# DE-270124.net
KiCad netlist of a schematic drawn in Altium Designer
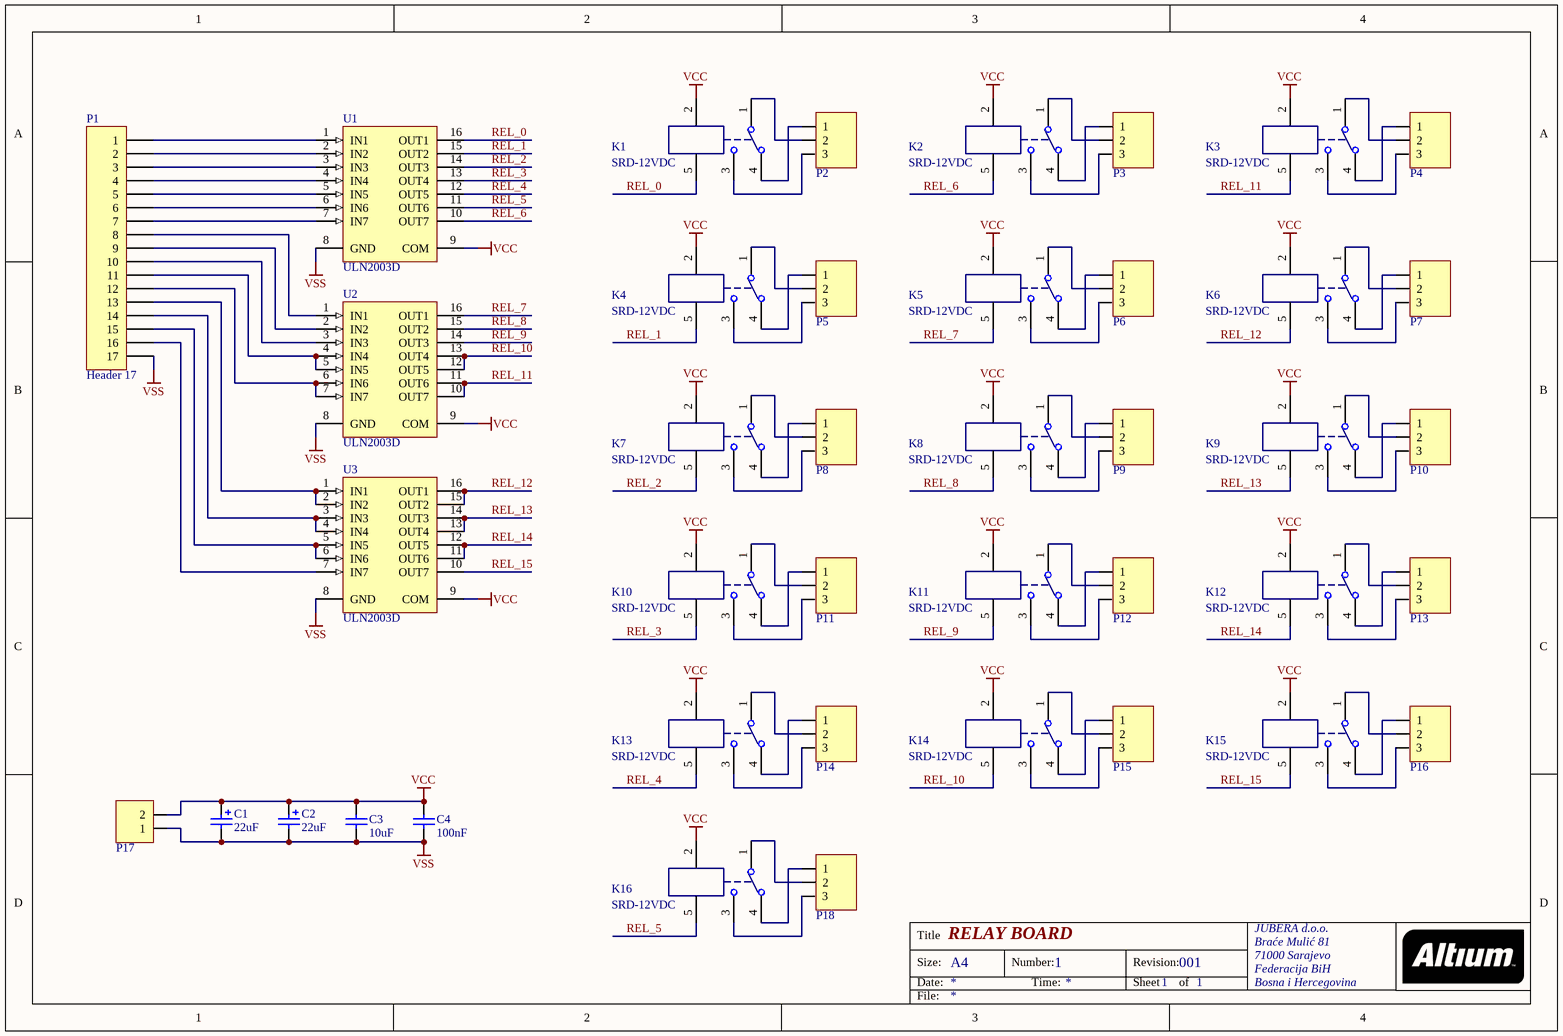
[diagram p0: DE-270124.SchDoc]

(export (version "E")
  (design (tool "Eeschema 10.0.6"))
  (components
    (comp (ref "C1")
      (value "22uF")
      (footprint "CAPPR2-5X11")
      (description "Aluminum Electrolytic Capacitor, Radial Style with Long Leads: 47uF, 35V")
      (fields (field (name "PUBLISHER") "Altium Limited"))
      (libsource (lib "DE-270124") (part "EKA00AA247F00"))
    )
    (comp (ref "C2")
      (value "22uF")
      (footprint "CAPPR2-5X11")
      (description "Aluminum Electrolytic Capacitor, Radial Style with Long Leads: 47uF, 35V")
      (fields (field (name "PUBLISHER") "Altium Limited"))
      (libsource (lib "DE-270124") (part "EKA00AA247F00"))
    )
    (comp (ref "C3")
      (value "10uF")
      (footprint "0805")
      (description "Ceramic Chip Capacitor - Standard")
      (fields (field (name "PUBLISHER") "Altium Limited"))
      (libsource (lib "DE-270124") (part "C0805"))
    )
    (comp (ref "C4")
      (value "100nF")
      (footprint "0603")
      (description "Ceramic Chip Capacitor - Standard")
      (fields (field (name "PUBLISHER") "Altium Limited"))
      (libsource (lib "DE-270124") (part "C0603"))
    )
    (comp (ref "K1")
      (value "SRD-12VDC")
      (footprint "SRD-12VDC-SL-O")
      (description "SPDT PCB relay 12Vc coil")
      (libsource (lib "DE-270124") (part "SRD-12VDC-SL-O"))
    )
    (comp (ref "K2")
      (value "SRD-12VDC")
      (footprint "SRD-12VDC-SL-O")
      (description "SPDT PCB relay 12Vc coil")
      (libsource (lib "DE-270124") (part "SRD-12VDC-SL-O"))
    )
    (comp (ref "K3")
      (value "SRD-12VDC")
      (footprint "SRD-12VDC-SL-O")
      (description "SPDT PCB relay 12Vc coil")
      (libsource (lib "DE-270124") (part "SRD-12VDC-SL-O"))
    )
    (comp (ref "K4")
      (value "SRD-12VDC")
      (footprint "SRD-12VDC-SL-O")
      (description "SPDT PCB relay 12Vc coil")
      (libsource (lib "DE-270124") (part "SRD-12VDC-SL-O"))
    )
    (comp (ref "K5")
      (value "SRD-12VDC")
      (footprint "SRD-12VDC-SL-O")
      (description "SPDT PCB relay 12Vc coil")
      (libsource (lib "DE-270124") (part "SRD-12VDC-SL-O"))
    )
    (comp (ref "K6")
      (value "SRD-12VDC")
      (footprint "SRD-12VDC-SL-O")
      (description "SPDT PCB relay 12Vc coil")
      (libsource (lib "DE-270124") (part "SRD-12VDC-SL-O"))
    )
    (comp (ref "K7")
      (value "SRD-12VDC")
      (footprint "SRD-12VDC-SL-O")
      (description "SPDT PCB relay 12Vc coil")
      (libsource (lib "DE-270124") (part "SRD-12VDC-SL-O"))
    )
    (comp (ref "K8")
      (value "SRD-12VDC")
      (footprint "SRD-12VDC-SL-O")
      (description "SPDT PCB relay 12Vc coil")
      (libsource (lib "DE-270124") (part "SRD-12VDC-SL-O"))
    )
    (comp (ref "K9")
      (value "SRD-12VDC")
      (footprint "SRD-12VDC-SL-O")
      (description "SPDT PCB relay 12Vc coil")
      (libsource (lib "DE-270124") (part "SRD-12VDC-SL-O"))
    )
    (comp (ref "K10")
      (value "SRD-12VDC")
      (footprint "SRD-12VDC-SL-O")
      (description "SPDT PCB relay 12Vc coil")
      (libsource (lib "DE-270124") (part "SRD-12VDC-SL-O"))
    )
    (comp (ref "K11")
      (value "SRD-12VDC")
      (footprint "SRD-12VDC-SL-O")
      (description "SPDT PCB relay 12Vc coil")
      (libsource (lib "DE-270124") (part "SRD-12VDC-SL-O"))
    )
    (comp (ref "K12")
      (value "SRD-12VDC")
      (footprint "SRD-12VDC-SL-O")
      (description "SPDT PCB relay 12Vc coil")
      (libsource (lib "DE-270124") (part "SRD-12VDC-SL-O"))
    )
    (comp (ref "K13")
      (value "SRD-12VDC")
      (footprint "SRD-12VDC-SL-O")
      (description "SPDT PCB relay 12Vc coil")
      (libsource (lib "DE-270124") (part "SRD-12VDC-SL-O"))
    )
    (comp (ref "K14")
      (value "SRD-12VDC")
      (footprint "SRD-12VDC-SL-O")
      (description "SPDT PCB relay 12Vc coil")
      (libsource (lib "DE-270124") (part "SRD-12VDC-SL-O"))
    )
    (comp (ref "K15")
      (value "SRD-12VDC")
      (footprint "SRD-12VDC-SL-O")
      (description "SPDT PCB relay 12Vc coil")
      (libsource (lib "DE-270124") (part "SRD-12VDC-SL-O"))
    )
    (comp (ref "K16")
      (value "SRD-12VDC")
      (footprint "SRD-12VDC-SL-O")
      (description "SPDT PCB relay 12Vc coil")
      (libsource (lib "DE-270124") (part "SRD-12VDC-SL-O"))
    )
    (comp (ref "P1")
      (value "Header 17")
      (footprint "HDR1X17")
      (description "Header, 17-Pin")
      (fields (field (name "PUBLISHER") "Altium Limited"))
      (libsource (lib "Miscellaneous Connectors") (part "Header 17"))
    )
    (comp (ref "P2")
      (value "TERMINAL BLOK 3")
      (footprint "TERMINAL BLOK 3")
      (description "3 pinski terminal blok konektor")
      (libsource (lib "DE-270124") (part "TERMINAL BLOK 3"))
    )
    (comp (ref "P3")
      (value "TERMINAL BLOK 3")
      (footprint "TERMINAL BLOK 3")
      (description "3 pinski terminal blok konektor")
      (libsource (lib "DE-270124") (part "TERMINAL BLOK 3"))
    )
    (comp (ref "P4")
      (value "TERMINAL BLOK 3")
      (footprint "TERMINAL BLOK 3")
      (description "3 pinski terminal blok konektor")
      (libsource (lib "DE-270124") (part "TERMINAL BLOK 3"))
    )
    (comp (ref "P5")
      (value "TERMINAL BLOK 3")
      (footprint "TERMINAL BLOK 3")
      (description "3 pinski terminal blok konektor")
      (libsource (lib "DE-270124") (part "TERMINAL BLOK 3"))
    )
    (comp (ref "P6")
      (value "TERMINAL BLOK 3")
      (footprint "TERMINAL BLOK 3")
      (description "3 pinski terminal blok konektor")
      (libsource (lib "DE-270124") (part "TERMINAL BLOK 3"))
    )
    (comp (ref "P7")
      (value "TERMINAL BLOK 3")
      (footprint "TERMINAL BLOK 3")
      (description "3 pinski terminal blok konektor")
      (libsource (lib "DE-270124") (part "TERMINAL BLOK 3"))
    )
    (comp (ref "P8")
      (value "TERMINAL BLOK 3")
      (footprint "TERMINAL BLOK 3")
      (description "3 pinski terminal blok konektor")
      (libsource (lib "DE-270124") (part "TERMINAL BLOK 3"))
    )
    (comp (ref "P9")
      (value "TERMINAL BLOK 3")
      (footprint "TERMINAL BLOK 3")
      (description "3 pinski terminal blok konektor")
      (libsource (lib "DE-270124") (part "TERMINAL BLOK 3"))
    )
    (comp (ref "P10")
      (value "TERMINAL BLOK 3")
      (footprint "TERMINAL BLOK 3")
      (description "3 pinski terminal blok konektor")
      (libsource (lib "DE-270124") (part "TERMINAL BLOK 3"))
    )
    (comp (ref "P11")
      (value "TERMINAL BLOK 3")
      (footprint "TERMINAL BLOK 3")
      (description "3 pinski terminal blok konektor")
      (libsource (lib "DE-270124") (part "TERMINAL BLOK 3"))
    )
    (comp (ref "P12")
      (value "TERMINAL BLOK 3")
      (footprint "TERMINAL BLOK 3")
      (description "3 pinski terminal blok konektor")
      (libsource (lib "DE-270124") (part "TERMINAL BLOK 3"))
    )
    (comp (ref "P13")
      (value "TERMINAL BLOK 3")
      (footprint "TERMINAL BLOK 3")
      (description "3 pinski terminal blok konektor")
      (libsource (lib "DE-270124") (part "TERMINAL BLOK 3"))
    )
    (comp (ref "P14")
      (value "TERMINAL BLOK 3")
      (footprint "TERMINAL BLOK 3")
      (description "3 pinski terminal blok konektor")
      (libsource (lib "DE-270124") (part "TERMINAL BLOK 3"))
    )
    (comp (ref "P15")
      (value "TERMINAL BLOK 3")
      (footprint "TERMINAL BLOK 3")
      (description "3 pinski terminal blok konektor")
      (libsource (lib "DE-270124") (part "TERMINAL BLOK 3"))
    )
    (comp (ref "P16")
      (value "TERMINAL BLOK 3")
      (footprint "TERMINAL BLOK 3")
      (description "3 pinski terminal blok konektor")
      (libsource (lib "DE-270124") (part "TERMINAL BLOK 3"))
    )
    (comp (ref "P17")
      (value "TERMINAL BLOK 2")
      (footprint "TERMINAL BLOK 2")
      (description "2 pinski terminal blok")
      (libsource (lib "DE-270124") (part "TERMINAL BLOK 2"))
    )
    (comp (ref "P18")
      (value "TERMINAL BLOK 3")
      (footprint "TERMINAL BLOK 3")
      (description "3 pinski terminal blok konektor")
      (libsource (lib "DE-270124") (part "TERMINAL BLOK 3"))
    )
    (comp (ref "U1")
      (value "ULN2003D")
      (footprint "SO16_N")
      (description "Seven Darlington Array")
      (fields (field (name "PUBLISHER") "Altium Limited"))
      (libsource (lib "DE-270124") (part "ULN2003D"))
    )
    (comp (ref "U2")
      (value "ULN2003D")
      (footprint "SO16_N")
      (description "Seven Darlington Array")
      (fields (field (name "PUBLISHER") "Altium Limited"))
      (libsource (lib "DE-270124") (part "ULN2003D"))
    )
    (comp (ref "U3")
      (value "ULN2003D")
      (footprint "SO16_N")
      (description "Seven Darlington Array")
      (fields (field (name "PUBLISHER") "Altium Limited"))
      (libsource (lib "DE-270124") (part "ULN2003D"))
    )
  )
  (nets
    (net (code "1") (name "/REL_0") (class "Default")
      (node (ref "K1") (pin "5") (pinfunction "5_5") (pintype "passive"))
      (node (ref "U1") (pin "16") (pinfunction "OUT1_16") (pintype "open_collector"))
    )
    (net (code "2") (name "/REL_1") (class "Default")
      (node (ref "K4") (pin "5") (pinfunction "5_5") (pintype "passive"))
      (node (ref "U1") (pin "15") (pinfunction "OUT2_15") (pintype "open_collector"))
    )
    (net (code "3") (name "/REL_2") (class "Default")
      (node (ref "K7") (pin "5") (pinfunction "5_5") (pintype "passive"))
      (node (ref "U1") (pin "14") (pinfunction "OUT3_14") (pintype "open_collector"))
    )
    (net (code "4") (name "/REL_3") (class "Default")
      (node (ref "K10") (pin "5") (pinfunction "5_5") (pintype "passive"))
      (node (ref "U1") (pin "13") (pinfunction "OUT4_13") (pintype "open_collector"))
    )
    (net (code "5") (name "/REL_4") (class "Default")
      (node (ref "K13") (pin "5") (pinfunction "5_5") (pintype "passive"))
      (node (ref "U1") (pin "12") (pinfunction "OUT5_12") (pintype "open_collector"))
    )
    (net (code "6") (name "/REL_5") (class "Default")
      (node (ref "K16") (pin "5") (pinfunction "5_5") (pintype "passive"))
      (node (ref "U1") (pin "11") (pinfunction "OUT6_11") (pintype "open_collector"))
    )
    (net (code "7") (name "/REL_6") (class "Default")
      (node (ref "K2") (pin "5") (pinfunction "5_5") (pintype "passive"))
      (node (ref "U1") (pin "10") (pinfunction "OUT7_10") (pintype "open_collector"))
    )
    (net (code "8") (name "/REL_7") (class "Default")
      (node (ref "K5") (pin "5") (pinfunction "5_5") (pintype "passive"))
      (node (ref "U2") (pin "16") (pinfunction "OUT1_16") (pintype "open_collector"))
    )
    (net (code "9") (name "/REL_8") (class "Default")
      (node (ref "K8") (pin "5") (pinfunction "5_5") (pintype "passive"))
      (node (ref "U2") (pin "15") (pinfunction "OUT2_15") (pintype "open_collector"))
    )
    (net (code "10") (name "/REL_9") (class "Default")
      (node (ref "K11") (pin "5") (pinfunction "5_5") (pintype "passive"))
      (node (ref "U2") (pin "14") (pinfunction "OUT3_14") (pintype "open_collector"))
    )
    (net (code "11") (name "/REL_10") (class "Default")
      (node (ref "K14") (pin "5") (pinfunction "5_5") (pintype "passive"))
      (node (ref "U2") (pin "12") (pinfunction "OUT5_12") (pintype "open_collector"))
      (node (ref "U2") (pin "13") (pinfunction "OUT4_13") (pintype "open_collector"))
    )
    (net (code "12") (name "/REL_11") (class "Default")
      (node (ref "K3") (pin "5") (pinfunction "5_5") (pintype "passive"))
      (node (ref "U2") (pin "10") (pinfunction "OUT7_10") (pintype "open_collector"))
      (node (ref "U2") (pin "11") (pinfunction "OUT6_11") (pintype "open_collector"))
    )
    (net (code "13") (name "/REL_12") (class "Default")
      (node (ref "K6") (pin "5") (pinfunction "5_5") (pintype "passive"))
      (node (ref "U3") (pin "15") (pinfunction "OUT2_15") (pintype "open_collector"))
      (node (ref "U3") (pin "16") (pinfunction "OUT1_16") (pintype "open_collector"))
    )
    (net (code "14") (name "/REL_13") (class "Default")
      (node (ref "K9") (pin "5") (pinfunction "5_5") (pintype "passive"))
      (node (ref "U3") (pin "13") (pinfunction "OUT4_13") (pintype "open_collector"))
      (node (ref "U3") (pin "14") (pinfunction "OUT3_14") (pintype "open_collector"))
    )
    (net (code "15") (name "/REL_14") (class "Default")
      (node (ref "K12") (pin "5") (pinfunction "5_5") (pintype "passive"))
      (node (ref "U3") (pin "11") (pinfunction "OUT6_11") (pintype "open_collector"))
      (node (ref "U3") (pin "12") (pinfunction "OUT5_12") (pintype "open_collector"))
    )
    (net (code "16") (name "/REL_15") (class "Default")
      (node (ref "K15") (pin "5") (pinfunction "5_5") (pintype "passive"))
      (node (ref "U3") (pin "10") (pinfunction "OUT7_10") (pintype "open_collector"))
    )
    (net (code "17") (name "Net-(K1-Pad1)") (class "Default")
      (node (ref "K1") (pin "1") (pinfunction "1_1") (pintype "passive"))
      (node (ref "P2") (pin "2") (pinfunction "2_2") (pintype "passive"))
    )
    (net (code "18") (name "Net-(K1-Pad3)") (class "Default")
      (node (ref "K1") (pin "3") (pinfunction "3_3") (pintype "passive"))
      (node (ref "P2") (pin "3") (pinfunction "3_3") (pintype "passive"))
    )
    (net (code "19") (name "Net-(K1-Pad4)") (class "Default")
      (node (ref "K1") (pin "4") (pinfunction "4_4") (pintype "passive"))
      (node (ref "P2") (pin "1") (pinfunction "1_1") (pintype "passive"))
    )
    (net (code "20") (name "Net-(K2-Pad1)") (class "Default")
      (node (ref "K2") (pin "1") (pinfunction "1_1") (pintype "passive"))
      (node (ref "P3") (pin "2") (pinfunction "2_2") (pintype "passive"))
    )
    (net (code "21") (name "Net-(K2-Pad3)") (class "Default")
      (node (ref "K2") (pin "3") (pinfunction "3_3") (pintype "passive"))
      (node (ref "P3") (pin "3") (pinfunction "3_3") (pintype "passive"))
    )
    (net (code "22") (name "Net-(K2-Pad4)") (class "Default")
      (node (ref "K2") (pin "4") (pinfunction "4_4") (pintype "passive"))
      (node (ref "P3") (pin "1") (pinfunction "1_1") (pintype "passive"))
    )
    (net (code "23") (name "Net-(K3-Pad1)") (class "Default")
      (node (ref "K3") (pin "1") (pinfunction "1_1") (pintype "passive"))
      (node (ref "P4") (pin "2") (pinfunction "2_2") (pintype "passive"))
    )
    (net (code "24") (name "Net-(K3-Pad3)") (class "Default")
      (node (ref "K3") (pin "3") (pinfunction "3_3") (pintype "passive"))
      (node (ref "P4") (pin "3") (pinfunction "3_3") (pintype "passive"))
    )
    (net (code "25") (name "Net-(K3-Pad4)") (class "Default")
      (node (ref "K3") (pin "4") (pinfunction "4_4") (pintype "passive"))
      (node (ref "P4") (pin "1") (pinfunction "1_1") (pintype "passive"))
    )
    (net (code "26") (name "Net-(K4-Pad1)") (class "Default")
      (node (ref "K4") (pin "1") (pinfunction "1_1") (pintype "passive"))
      (node (ref "P5") (pin "2") (pinfunction "2_2") (pintype "passive"))
    )
    (net (code "27") (name "Net-(K4-Pad3)") (class "Default")
      (node (ref "K4") (pin "3") (pinfunction "3_3") (pintype "passive"))
      (node (ref "P5") (pin "3") (pinfunction "3_3") (pintype "passive"))
    )
    (net (code "28") (name "Net-(K4-Pad4)") (class "Default")
      (node (ref "K4") (pin "4") (pinfunction "4_4") (pintype "passive"))
      (node (ref "P5") (pin "1") (pinfunction "1_1") (pintype "passive"))
    )
    (net (code "29") (name "Net-(K5-Pad1)") (class "Default")
      (node (ref "K5") (pin "1") (pinfunction "1_1") (pintype "passive"))
      (node (ref "P6") (pin "2") (pinfunction "2_2") (pintype "passive"))
    )
    (net (code "30") (name "Net-(K5-Pad3)") (class "Default")
      (node (ref "K5") (pin "3") (pinfunction "3_3") (pintype "passive"))
      (node (ref "P6") (pin "3") (pinfunction "3_3") (pintype "passive"))
    )
    (net (code "31") (name "Net-(K5-Pad4)") (class "Default")
      (node (ref "K5") (pin "4") (pinfunction "4_4") (pintype "passive"))
      (node (ref "P6") (pin "1") (pinfunction "1_1") (pintype "passive"))
    )
    (net (code "32") (name "Net-(K6-Pad1)") (class "Default")
      (node (ref "K6") (pin "1") (pinfunction "1_1") (pintype "passive"))
      (node (ref "P7") (pin "2") (pinfunction "2_2") (pintype "passive"))
    )
    (net (code "33") (name "Net-(K6-Pad3)") (class "Default")
      (node (ref "K6") (pin "3") (pinfunction "3_3") (pintype "passive"))
      (node (ref "P7") (pin "3") (pinfunction "3_3") (pintype "passive"))
    )
    (net (code "34") (name "Net-(K6-Pad4)") (class "Default")
      (node (ref "K6") (pin "4") (pinfunction "4_4") (pintype "passive"))
      (node (ref "P7") (pin "1") (pinfunction "1_1") (pintype "passive"))
    )
    (net (code "35") (name "Net-(K7-Pad1)") (class "Default")
      (node (ref "K7") (pin "1") (pinfunction "1_1") (pintype "passive"))
      (node (ref "P8") (pin "2") (pinfunction "2_2") (pintype "passive"))
    )
    (net (code "36") (name "Net-(K7-Pad3)") (class "Default")
      (node (ref "K7") (pin "3") (pinfunction "3_3") (pintype "passive"))
      (node (ref "P8") (pin "3") (pinfunction "3_3") (pintype "passive"))
    )
    (net (code "37") (name "Net-(K7-Pad4)") (class "Default")
      (node (ref "K7") (pin "4") (pinfunction "4_4") (pintype "passive"))
      (node (ref "P8") (pin "1") (pinfunction "1_1") (pintype "passive"))
    )
    (net (code "38") (name "Net-(K8-Pad1)") (class "Default")
      (node (ref "K8") (pin "1") (pinfunction "1_1") (pintype "passive"))
      (node (ref "P9") (pin "2") (pinfunction "2_2") (pintype "passive"))
    )
    (net (code "39") (name "Net-(K8-Pad3)") (class "Default")
      (node (ref "K8") (pin "3") (pinfunction "3_3") (pintype "passive"))
      (node (ref "P9") (pin "3") (pinfunction "3_3") (pintype "passive"))
    )
    (net (code "40") (name "Net-(K8-Pad4)") (class "Default")
      (node (ref "K8") (pin "4") (pinfunction "4_4") (pintype "passive"))
      (node (ref "P9") (pin "1") (pinfunction "1_1") (pintype "passive"))
    )
    (net (code "41") (name "Net-(K9-Pad1)") (class "Default")
      (node (ref "K9") (pin "1") (pinfunction "1_1") (pintype "passive"))
      (node (ref "P10") (pin "2") (pinfunction "2_2") (pintype "passive"))
    )
    (net (code "42") (name "Net-(K9-Pad3)") (class "Default")
      (node (ref "K9") (pin "3") (pinfunction "3_3") (pintype "passive"))
      (node (ref "P10") (pin "3") (pinfunction "3_3") (pintype "passive"))
    )
    (net (code "43") (name "Net-(K9-Pad4)") (class "Default")
      (node (ref "K9") (pin "4") (pinfunction "4_4") (pintype "passive"))
      (node (ref "P10") (pin "1") (pinfunction "1_1") (pintype "passive"))
    )
    (net (code "44") (name "Net-(K10-Pad1)") (class "Default")
      (node (ref "K10") (pin "1") (pinfunction "1_1") (pintype "passive"))
      (node (ref "P11") (pin "2") (pinfunction "2_2") (pintype "passive"))
    )
    (net (code "45") (name "Net-(K10-Pad3)") (class "Default")
      (node (ref "K10") (pin "3") (pinfunction "3_3") (pintype "passive"))
      (node (ref "P11") (pin "3") (pinfunction "3_3") (pintype "passive"))
    )
    (net (code "46") (name "Net-(K10-Pad4)") (class "Default")
      (node (ref "K10") (pin "4") (pinfunction "4_4") (pintype "passive"))
      (node (ref "P11") (pin "1") (pinfunction "1_1") (pintype "passive"))
    )
    (net (code "47") (name "Net-(K11-Pad1)") (class "Default")
      (node (ref "K11") (pin "1") (pinfunction "1_1") (pintype "passive"))
      (node (ref "P12") (pin "2") (pinfunction "2_2") (pintype "passive"))
    )
    (net (code "48") (name "Net-(K11-Pad3)") (class "Default")
      (node (ref "K11") (pin "3") (pinfunction "3_3") (pintype "passive"))
      (node (ref "P12") (pin "3") (pinfunction "3_3") (pintype "passive"))
    )
    (net (code "49") (name "Net-(K11-Pad4)") (class "Default")
      (node (ref "K11") (pin "4") (pinfunction "4_4") (pintype "passive"))
      (node (ref "P12") (pin "1") (pinfunction "1_1") (pintype "passive"))
    )
    (net (code "50") (name "Net-(K12-Pad1)") (class "Default")
      (node (ref "K12") (pin "1") (pinfunction "1_1") (pintype "passive"))
      (node (ref "P13") (pin "2") (pinfunction "2_2") (pintype "passive"))
    )
    (net (code "51") (name "Net-(K12-Pad3)") (class "Default")
      (node (ref "K12") (pin "3") (pinfunction "3_3") (pintype "passive"))
      (node (ref "P13") (pin "3") (pinfunction "3_3") (pintype "passive"))
    )
    (net (code "52") (name "Net-(K12-Pad4)") (class "Default")
      (node (ref "K12") (pin "4") (pinfunction "4_4") (pintype "passive"))
      (node (ref "P13") (pin "1") (pinfunction "1_1") (pintype "passive"))
    )
    (net (code "53") (name "Net-(K13-Pad1)") (class "Default")
      (node (ref "K13") (pin "1") (pinfunction "1_1") (pintype "passive"))
      (node (ref "P14") (pin "2") (pinfunction "2_2") (pintype "passive"))
    )
    (net (code "54") (name "Net-(K13-Pad3)") (class "Default")
      (node (ref "K13") (pin "3") (pinfunction "3_3") (pintype "passive"))
      (node (ref "P14") (pin "3") (pinfunction "3_3") (pintype "passive"))
    )
    (net (code "55") (name "Net-(K13-Pad4)") (class "Default")
      (node (ref "K13") (pin "4") (pinfunction "4_4") (pintype "passive"))
      (node (ref "P14") (pin "1") (pinfunction "1_1") (pintype "passive"))
    )
    (net (code "56") (name "Net-(K14-Pad1)") (class "Default")
      (node (ref "K14") (pin "1") (pinfunction "1_1") (pintype "passive"))
      (node (ref "P15") (pin "2") (pinfunction "2_2") (pintype "passive"))
    )
    (net (code "57") (name "Net-(K14-Pad3)") (class "Default")
      (node (ref "K14") (pin "3") (pinfunction "3_3") (pintype "passive"))
      (node (ref "P15") (pin "3") (pinfunction "3_3") (pintype "passive"))
    )
    (net (code "58") (name "Net-(K14-Pad4)") (class "Default")
      (node (ref "K14") (pin "4") (pinfunction "4_4") (pintype "passive"))
      (node (ref "P15") (pin "1") (pinfunction "1_1") (pintype "passive"))
    )
    (net (code "59") (name "Net-(K15-Pad1)") (class "Default")
      (node (ref "K15") (pin "1") (pinfunction "1_1") (pintype "passive"))
      (node (ref "P16") (pin "2") (pinfunction "2_2") (pintype "passive"))
    )
    (net (code "60") (name "Net-(K15-Pad3)") (class "Default")
      (node (ref "K15") (pin "3") (pinfunction "3_3") (pintype "passive"))
      (node (ref "P16") (pin "3") (pinfunction "3_3") (pintype "passive"))
    )
    (net (code "61") (name "Net-(K15-Pad4)") (class "Default")
      (node (ref "K15") (pin "4") (pinfunction "4_4") (pintype "passive"))
      (node (ref "P16") (pin "1") (pinfunction "1_1") (pintype "passive"))
    )
    (net (code "62") (name "Net-(K16-Pad1)") (class "Default")
      (node (ref "K16") (pin "1") (pinfunction "1_1") (pintype "passive"))
      (node (ref "P18") (pin "2") (pinfunction "2_2") (pintype "passive"))
    )
    (net (code "63") (name "Net-(K16-Pad3)") (class "Default")
      (node (ref "K16") (pin "3") (pinfunction "3_3") (pintype "passive"))
      (node (ref "P18") (pin "3") (pinfunction "3_3") (pintype "passive"))
    )
    (net (code "64") (name "Net-(K16-Pad4)") (class "Default")
      (node (ref "K16") (pin "4") (pinfunction "4_4") (pintype "passive"))
      (node (ref "P18") (pin "1") (pinfunction "1_1") (pintype "passive"))
    )
    (net (code "65") (name "Net-(U1-IN1)") (class "Default")
      (node (ref "P1") (pin "1") (pinfunction "1_1") (pintype "passive"))
      (node (ref "U1") (pin "1") (pinfunction "IN1_1") (pintype "input"))
    )
    (net (code "66") (name "Net-(U1-IN2)") (class "Default")
      (node (ref "P1") (pin "2") (pinfunction "2_2") (pintype "passive"))
      (node (ref "U1") (pin "2") (pinfunction "IN2_2") (pintype "input"))
    )
    (net (code "67") (name "Net-(U1-IN3)") (class "Default")
      (node (ref "P1") (pin "3") (pinfunction "3_3") (pintype "passive"))
      (node (ref "U1") (pin "3") (pinfunction "IN3_3") (pintype "input"))
    )
    (net (code "68") (name "Net-(U1-IN4)") (class "Default")
      (node (ref "P1") (pin "4") (pinfunction "4_4") (pintype "passive"))
      (node (ref "U1") (pin "4") (pinfunction "IN4_4") (pintype "input"))
    )
    (net (code "69") (name "Net-(U1-IN5)") (class "Default")
      (node (ref "P1") (pin "5") (pinfunction "5_5") (pintype "passive"))
      (node (ref "U1") (pin "5") (pinfunction "IN5_5") (pintype "input"))
    )
    (net (code "70") (name "Net-(U1-IN6)") (class "Default")
      (node (ref "P1") (pin "6") (pinfunction "6_6") (pintype "passive"))
      (node (ref "U1") (pin "6") (pinfunction "IN6_6") (pintype "input"))
    )
    (net (code "71") (name "Net-(U1-IN7)") (class "Default")
      (node (ref "P1") (pin "7") (pinfunction "7_7") (pintype "passive"))
      (node (ref "U1") (pin "7") (pinfunction "IN7_7") (pintype "input"))
    )
    (net (code "72") (name "Net-(U2-IN1)") (class "Default")
      (node (ref "P1") (pin "8") (pinfunction "8_8") (pintype "passive"))
      (node (ref "U2") (pin "1") (pinfunction "IN1_1") (pintype "input"))
    )
    (net (code "73") (name "Net-(U2-IN2)") (class "Default")
      (node (ref "P1") (pin "9") (pinfunction "9_9") (pintype "passive"))
      (node (ref "U2") (pin "2") (pinfunction "IN2_2") (pintype "input"))
    )
    (net (code "74") (name "Net-(U2-IN3)") (class "Default")
      (node (ref "P1") (pin "10") (pinfunction "10_10") (pintype "passive"))
      (node (ref "U2") (pin "3") (pinfunction "IN3_3") (pintype "input"))
    )
    (net (code "75") (name "Net-(U2-IN4)") (class "Default")
      (node (ref "P1") (pin "11") (pinfunction "11_11") (pintype "passive"))
      (node (ref "U2") (pin "4") (pinfunction "IN4_4") (pintype "input"))
      (node (ref "U2") (pin "5") (pinfunction "IN5_5") (pintype "input"))
    )
    (net (code "76") (name "Net-(U2-IN6)") (class "Default")
      (node (ref "P1") (pin "12") (pinfunction "12_12") (pintype "passive"))
      (node (ref "U2") (pin "6") (pinfunction "IN6_6") (pintype "input"))
      (node (ref "U2") (pin "7") (pinfunction "IN7_7") (pintype "input"))
    )
    (net (code "77") (name "Net-(U3-IN1)") (class "Default")
      (node (ref "P1") (pin "13") (pinfunction "13_13") (pintype "passive"))
      (node (ref "U3") (pin "1") (pinfunction "IN1_1") (pintype "input"))
      (node (ref "U3") (pin "2") (pinfunction "IN2_2") (pintype "input"))
    )
    (net (code "78") (name "Net-(U3-IN3)") (class "Default")
      (node (ref "P1") (pin "14") (pinfunction "14_14") (pintype "passive"))
      (node (ref "U3") (pin "3") (pinfunction "IN3_3") (pintype "input"))
      (node (ref "U3") (pin "4") (pinfunction "IN4_4") (pintype "input"))
    )
    (net (code "79") (name "Net-(U3-IN5)") (class "Default")
      (node (ref "P1") (pin "15") (pinfunction "15_15") (pintype "passive"))
      (node (ref "U3") (pin "5") (pinfunction "IN5_5") (pintype "input"))
      (node (ref "U3") (pin "6") (pinfunction "IN6_6") (pintype "input"))
    )
    (net (code "80") (name "Net-(U3-IN7)") (class "Default")
      (node (ref "P1") (pin "16") (pinfunction "16_16") (pintype "passive"))
      (node (ref "U3") (pin "7") (pinfunction "IN7_7") (pintype "input"))
    )
    (net (code "81") (name "VCC") (class "Default")
      (node (ref "C1") (pin "1") (pinfunction "1_1") (pintype "passive"))
      (node (ref "C2") (pin "1") (pinfunction "1_1") (pintype "passive"))
      (node (ref "C3") (pin "2") (pinfunction "2_2") (pintype "passive"))
      (node (ref "C4") (pin "2") (pinfunction "2_2") (pintype "passive"))
      (node (ref "K1") (pin "2") (pinfunction "2_2") (pintype "passive"))
      (node (ref "K10") (pin "2") (pinfunction "2_2") (pintype "passive"))
      (node (ref "K11") (pin "2") (pinfunction "2_2") (pintype "passive"))
      (node (ref "K12") (pin "2") (pinfunction "2_2") (pintype "passive"))
      (node (ref "K13") (pin "2") (pinfunction "2_2") (pintype "passive"))
      (node (ref "K14") (pin "2") (pinfunction "2_2") (pintype "passive"))
      (node (ref "K15") (pin "2") (pinfunction "2_2") (pintype "passive"))
      (node (ref "K16") (pin "2") (pinfunction "2_2") (pintype "passive"))
      (node (ref "K2") (pin "2") (pinfunction "2_2") (pintype "passive"))
      (node (ref "K3") (pin "2") (pinfunction "2_2") (pintype "passive"))
      (node (ref "K4") (pin "2") (pinfunction "2_2") (pintype "passive"))
      (node (ref "K5") (pin "2") (pinfunction "2_2") (pintype "passive"))
      (node (ref "K6") (pin "2") (pinfunction "2_2") (pintype "passive"))
      (node (ref "K7") (pin "2") (pinfunction "2_2") (pintype "passive"))
      (node (ref "K8") (pin "2") (pinfunction "2_2") (pintype "passive"))
      (node (ref "K9") (pin "2") (pinfunction "2_2") (pintype "passive"))
      (node (ref "P17") (pin "2") (pinfunction "2_2") (pintype "passive"))
      (node (ref "U1") (pin "9") (pinfunction "COM_9") (pintype "passive"))
      (node (ref "U2") (pin "9") (pinfunction "COM_9") (pintype "passive"))
      (node (ref "U3") (pin "9") (pinfunction "COM_9") (pintype "passive"))
    )
    (net (code "82") (name "VSS") (class "Default")
      (node (ref "C1") (pin "2") (pinfunction "2_2") (pintype "passive"))
      (node (ref "C2") (pin "2") (pinfunction "2_2") (pintype "passive"))
      (node (ref "C3") (pin "1") (pinfunction "1_1") (pintype "passive"))
      (node (ref "C4") (pin "1") (pinfunction "1_1") (pintype "passive"))
      (node (ref "P1") (pin "17") (pinfunction "17_17") (pintype "passive"))
      (node (ref "P17") (pin "1") (pinfunction "1_1") (pintype "passive"))
      (node (ref "U1") (pin "8") (pinfunction "GND_8") (pintype "power_in"))
      (node (ref "U2") (pin "8") (pinfunction "GND_8") (pintype "power_in"))
      (node (ref "U3") (pin "8") (pinfunction "GND_8") (pintype "power_in"))
    )
  )
)
